# Main.net
KiCad netlist of a schematic drawn in Altium Designer
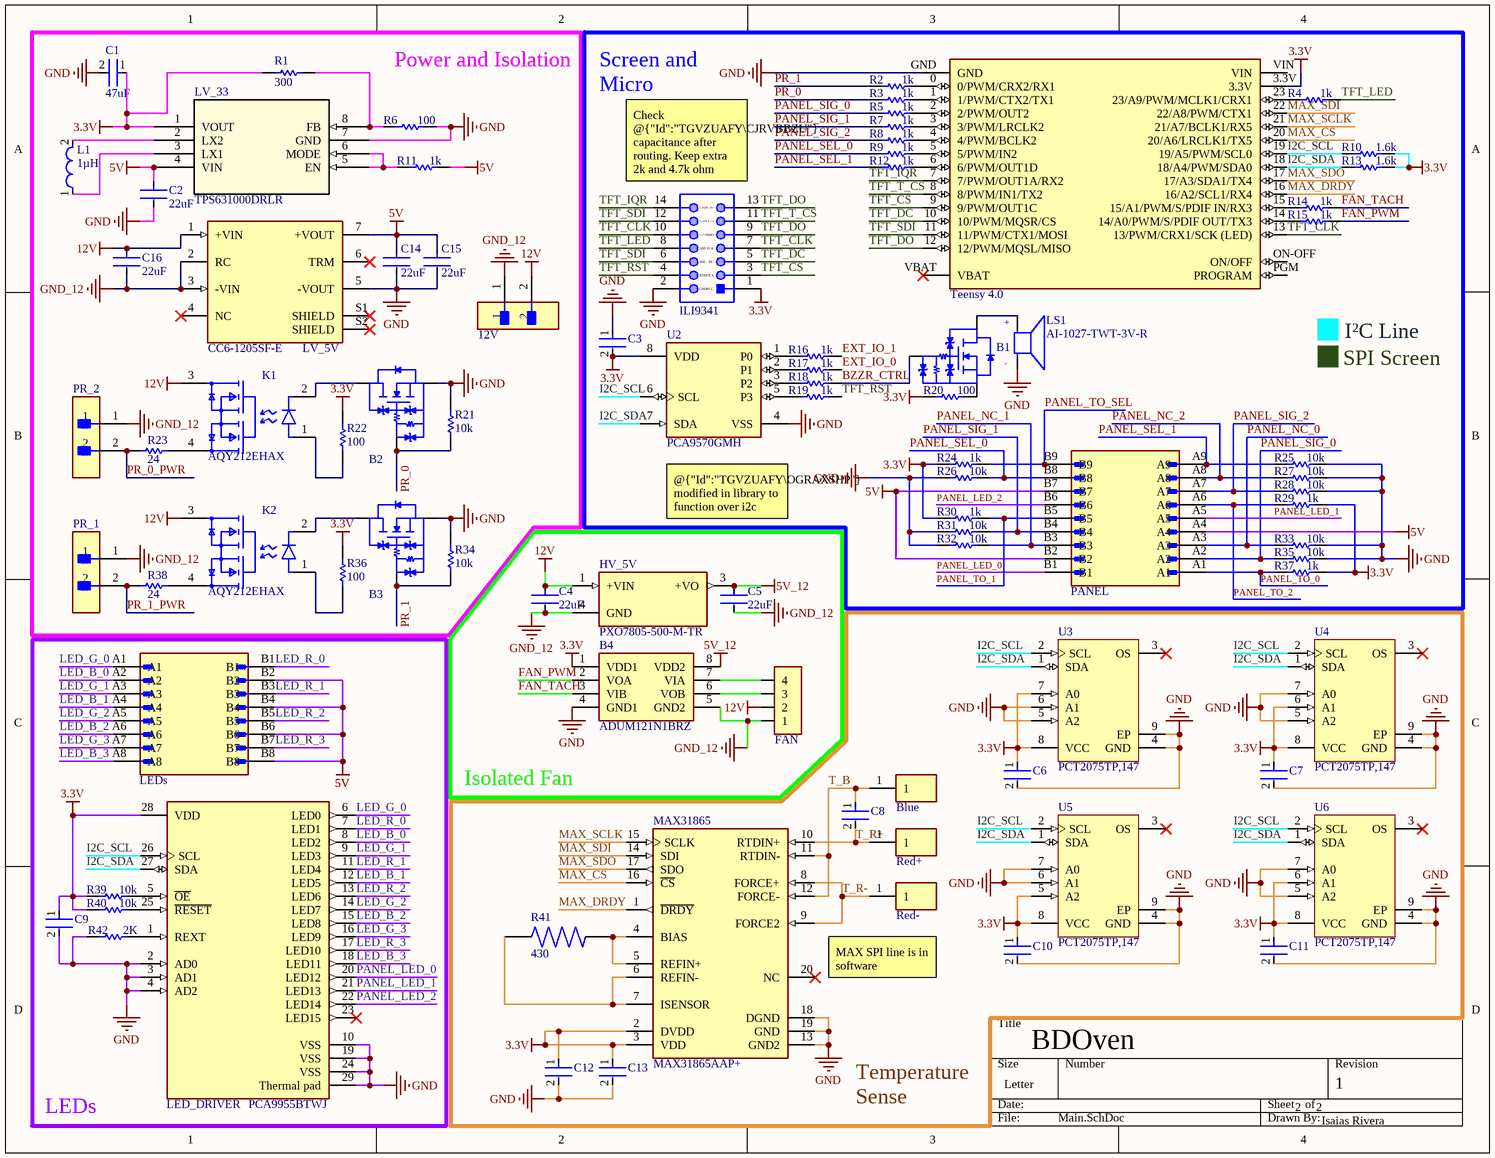
[diagram p0: Main.SchDoc]

(export (version "E")
  (design (tool "Eeschema 10.0.6"))
  (components
    (comp (ref "12V")
      (value "105313-1302")
      (footprint "FP-105313-1102-MFG")
      (description "Nano-Fit Right Angle Header Through Hole 2.50mm Pitch Single Row 2 Circuits 0.76")
      (libsource (lib "") (part "3bc925449376181038e59eaffc5286c_1"))
    )
    (comp (ref "B1")
      (value "SSM3K357R,LF")
      (footprint "SOTFL95P240X88-3N")
      (description "Trans MOSFET N-CH Si 60V 0.65A Automotive 3-Pin SOT-23F T/R")
      (libsource (lib "IIT Motorsports") (part "SSM3K357R,LF"))
    )
    (comp (ref "B2")
      (value "SSM3K357R,LF")
      (footprint "SOTFL95P240X88-3N")
      (description "Trans MOSFET N-CH Si 60V 0.65A Automotive 3-Pin SOT-23F T/R")
      (libsource (lib "IIT Motorsports") (part "SSM3K357R,LF"))
    )
    (comp (ref "B3")
      (value "SSM3K357R,LF")
      (footprint "SOTFL95P240X88-3N")
      (description "Trans MOSFET N-CH Si 60V 0.65A Automotive 3-Pin SOT-23F T/R")
      (libsource (lib "IIT Motorsports") (part "SSM3K357R,LF"))
    )
    (comp (ref "B4")
      (value "ADUM121N1BRZ")
      (footprint "SOIC127P600X175-8N")
      (description "Digital Isolator CMOS 2-CH 150Mbps 8-Pin SOIC N Tube")
      (fields (field (name "MOUSER PART NUMBER") "584-ADUM121N1BRZ"))
      (libsource (lib "IIT Motorsports") (part "ADUM121N1BRZ"))
    )
    (comp (ref "Blue")
      (value "Blue Connector")
      (footprint "8191")
      (description "TERM SCREW 6-32 4 PIN PCB")
      (fields (field (name "MOUSER PART NUMBER") "534-8191") (field (name "MANUFACTURER_PART_NUMBER") "8191"))
      (libsource (lib "IIT Motorsports") (part "8191"))
    )
    (comp (ref "C1")
      (value "47uF")
      (footprint "FP-CL31-IPC_C")
      (description "Cap Ceramic 47uF 10V X5R 20% SMD 1206 85°C Embossed Plastic T/R")
      (libsource (lib "IIT Motorsports") (part "b4654b650e69147ec39a6b967a45e02"))
    )
    (comp (ref "C2")
      (value "22uF")
      (footprint "FP-CL31H-0_2-IPC_C")
      (description "Ceramic capacitor SMD 1206 - 22uF/25V X5R# K +-10% Samsung, RoHS")
      (libsource (lib "IIT Motorsports") (part "11868f565c42a9108669ba33697ecf6"))
    )
    (comp (ref "C3")
      (value "CL10B104JB8NNNC")
      (footprint "FP-CL10-0_1-MFG")
      (description "CAP CER 0.1UF 50V X7R 0603")
      (fields
        (field (name "MANUFACTURER") "Samsung Electro-Mechanics America, Inc")
        (field (name "OCTOPART") "https://octopart.com/cl10b104jb8nnnc-samsung-9302151")
      )
      (libsource (lib "Altium Content Vault") (part "b4654b650e69147ec39a6b967a45e02"))
    )
    (comp (ref "C4")
      (value "22uF")
      (footprint "FP-CL31H-0_2-IPC_C")
      (description "Ceramic capacitor SMD 1206 - 22uF/25V X5R# K +-10% Samsung, RoHS")
      (libsource (lib "IIT Motorsports") (part "11868f565c42a9108669ba33697ecf6"))
    )
    (comp (ref "C5")
      (value "22uF")
      (footprint "FP-CL31H-0_2-IPC_C")
      (description "Ceramic capacitor SMD 1206 - 22uF/25V X5R# K +-10% Samsung, RoHS")
      (libsource (lib "IIT Motorsports") (part "11868f565c42a9108669ba33697ecf6"))
    )
    (comp (ref "C6")
      (value "CL10B104JB8NNNC")
      (footprint "FP-CL10-0_1-MFG")
      (description "CAP CER 0.1UF 50V X7R 0603")
      (fields
        (field (name "MANUFACTURER") "Samsung Electro-Mechanics America, Inc")
        (field (name "OCTOPART") "https://octopart.com/cl10b104jb8nnnc-samsung-9302151")
      )
      (libsource (lib "Altium Content Vault") (part "b4654b650e69147ec39a6b967a45e02"))
    )
    (comp (ref "C7")
      (value "CL10B104JB8NNNC")
      (footprint "FP-CL10-0_1-MFG")
      (description "CAP CER 0.1UF 50V X7R 0603")
      (fields
        (field (name "MANUFACTURER") "Samsung Electro-Mechanics America, Inc")
        (field (name "OCTOPART") "https://octopart.com/cl10b104jb8nnnc-samsung-9302151")
      )
      (libsource (lib "Altium Content Vault") (part "b4654b650e69147ec39a6b967a45e02"))
    )
    (comp (ref "C8")
      (value "CL10B104JB8NNNC")
      (footprint "FP-CL10-0_1-MFG")
      (description "CAP CER 0.1UF 50V X7R 0603")
      (fields
        (field (name "MANUFACTURER") "Samsung Electro-Mechanics America, Inc")
        (field (name "OCTOPART") "https://octopart.com/cl10b104jb8nnnc-samsung-9302151")
      )
      (libsource (lib "Altium Content Vault") (part "b4654b650e69147ec39a6b967a45e02"))
    )
    (comp (ref "C9")
      (value "CL10B104JB8NNNC")
      (footprint "FP-CL10-0_1-MFG")
      (description "CAP CER 0.1UF 50V X7R 0603")
      (fields
        (field (name "MANUFACTURER") "Samsung Electro-Mechanics America, Inc")
        (field (name "OCTOPART") "https://octopart.com/cl10b104jb8nnnc-samsung-9302151")
      )
      (libsource (lib "Altium Content Vault") (part "b4654b650e69147ec39a6b967a45e02"))
    )
    (comp (ref "C10")
      (value "CL10B104JB8NNNC")
      (footprint "FP-CL10-0_1-MFG")
      (description "CAP CER 0.1UF 50V X7R 0603")
      (fields
        (field (name "MANUFACTURER") "Samsung Electro-Mechanics America, Inc")
        (field (name "OCTOPART") "https://octopart.com/cl10b104jb8nnnc-samsung-9302151")
      )
      (libsource (lib "Altium Content Vault") (part "b4654b650e69147ec39a6b967a45e02"))
    )
    (comp (ref "C11")
      (value "CL10B104JB8NNNC")
      (footprint "FP-CL10-0_1-MFG")
      (description "CAP CER 0.1UF 50V X7R 0603")
      (fields
        (field (name "MANUFACTURER") "Samsung Electro-Mechanics America, Inc")
        (field (name "OCTOPART") "https://octopart.com/cl10b104jb8nnnc-samsung-9302151")
      )
      (libsource (lib "Altium Content Vault") (part "b4654b650e69147ec39a6b967a45e02"))
    )
    (comp (ref "C12")
      (value "CL10B104JB8NNNC")
      (footprint "FP-CL10-0_1-MFG")
      (description "CAP CER 0.1UF 50V X7R 0603")
      (fields
        (field (name "MANUFACTURER") "Samsung Electro-Mechanics America, Inc")
        (field (name "OCTOPART") "https://octopart.com/cl10b104jb8nnnc-samsung-9302151")
      )
      (libsource (lib "Altium Content Vault") (part "b4654b650e69147ec39a6b967a45e02"))
    )
    (comp (ref "C13")
      (value "CL10B104JB8NNNC")
      (footprint "FP-CL10-0_1-MFG")
      (description "CAP CER 0.1UF 50V X7R 0603")
      (fields
        (field (name "MANUFACTURER") "Samsung Electro-Mechanics America, Inc")
        (field (name "OCTOPART") "https://octopart.com/cl10b104jb8nnnc-samsung-9302151")
      )
      (libsource (lib "Altium Content Vault") (part "b4654b650e69147ec39a6b967a45e02"))
    )
    (comp (ref "C14")
      (value "22uF")
      (footprint "FP-CL31H-0_2-IPC_C")
      (description "Ceramic capacitor SMD 1206 - 22uF/25V X5R# K +-10% Samsung, RoHS")
      (libsource (lib "IIT Motorsports") (part "11868f565c42a9108669ba33697ecf6"))
    )
    (comp (ref "C15")
      (value "22uF")
      (footprint "FP-CL31H-0_2-IPC_C")
      (description "Ceramic capacitor SMD 1206 - 22uF/25V X5R# K +-10% Samsung, RoHS")
      (libsource (lib "IIT Motorsports") (part "11868f565c42a9108669ba33697ecf6"))
    )
    (comp (ref "C16")
      (value "22uF")
      (footprint "FP-CL31H-0_2-IPC_C")
      (description "Ceramic capacitor SMD 1206 - 22uF/25V X5R# K +-10% Samsung, RoHS")
      (libsource (lib "IIT Motorsports") (part "11868f565c42a9108669ba33697ecf6"))
    )
    (comp (ref "FAN")
      (value "47053-1000")
      (footprint "FP-47053-1000-MFG")
      (description "CONN HEADER VERT 4POS 2.54MM")
      (libsource (lib "IIT Motorsports") (part "299a8cea1bdcbc3624fe62c390fa72c"))
    )
    (comp (ref "HV_5V")
      (value "PXO7805-500-M-TR")
      (footprint "CONV_PXO7805-500-M-TR")
      (description "5 Vdc, 0.5 A, 2.5 W, 6.5~36 Vdc Input Range")
      (fields (field (name "MF") "{'manufacturer': u'CUI'}"))
      (libsource (lib "IIT Motorsports") (part "PXO7805-500-M-TR"))
    )
    (comp (ref "ILI9341")
      (value "61201421721")
      (footprint "61201421721")
      (description "Male Box Header WR-BHD, THT, Angled, pitch 2.54 mm, 14 pins")
      (libsource (lib "IIT Motorsports") (part "WE-CN-2P-M-R14"))
    )
    (comp (ref "K1")
      (value "AQY212EHAX")
      (footprint "FP-AQY212EHAX-MFG")
      (description "Relay Ssr 50MA 1.5V Dc-in 550MA 60V Ac/dc-out 4-PIN DIP SMD T/r")
      (libsource (lib "IIT Motorsports") (part "39108d2c2fe9c6c4263f1aa8ae40286"))
    )
    (comp (ref "K2")
      (value "AQY212EHAX")
      (footprint "FP-AQY212EHAX-MFG")
      (description "Relay Ssr 50MA 1.5V Dc-in 550MA 60V Ac/dc-out 4-PIN DIP SMD T/r")
      (libsource (lib "IIT Motorsports") (part "39108d2c2fe9c6c4263f1aa8ae40286"))
    )
    (comp (ref "L1")
      (value "1µH")
      (footprint "FP-DFE252012C-IPC_C")
      (description "Inductor Power Shielded Wirewound 1uH 20% 1MHz Metal 3.2A 0.042Ohm DCR 1008 T/R")
      (fields (field (name "TOLERANCE") "20%") (field (name "Comment") "DFE252012P-1R0M=P2"))
      (libsource (lib "IIT Motorsports") (part "725321dda6339637d4d059423bc1c3c"))
    )
    (comp (ref "LEDs")
      (value "76383-308LF")
      (footprint "AMPHENOL_91687-306LF")
      (description "Dubox®2.54mm, Board to Board Connector, Shrouded Header, Double Row, Right Angle.")
      (fields (field (name "MF") "{'manufacturer': u'Amphenol ICC (FCI)'}") (field (name "MP") "91687-306LF"))
      (libsource (lib "IIT Motorsports") (part "91687-306LF"))
    )
    (comp (ref "LED_DRIVER")
      (value "PCA9955BTWJ")
      (footprint "FP-SOT1172-3-IPC_A")
      (description "LED DRVR Boost 16-CH Individual RGB PWM 20V 0.03A 28-Pin HTSSOP T/R")
      (libsource (lib "IIT Motorsports") (part "4c3f84e579f246bc22335397bd4750c"))
    )
    (comp (ref "LS1")
      (value "AI-1027-TWT-3V-R")
      (footprint "XDCR_AI-1027-TWT-3V-R")
      (description "Audio Indicator Indicator Electromagnetic 3Vdc 30mA Pin 2Vdc 2500Hz to 2900Hz Through Hole")
      (fields (field (name "MF") "{'manufacturer': u'PUI Audio, Inc.'}"))
      (libsource (lib "IIT Motorsports") (part "AI-1027-TWT-3V-R"))
    )
    (comp (ref "LV_5V")
      (value "CC6-1205SF-E")
      (footprint "CONV_CC6-1205SF-E")
      (description "Module DC-DC 12VIN 1-OUT 5V 1.2A 6W 7-Pin DIP Module")
      (fields (field (name "MF") "{'manufacturer': u'TDK-Lambda'}"))
      (libsource (lib "IIT Motorsports") (part "CC6-1205SF-E"))
    )
    (comp (ref "LV_33")
      (value "TPS631000DRLR")
      (footprint "TPS631000DRLR_TEX")
      (description "1.5-A output current, high power density buck-boost converter 8-SOT-5X3 -40 to 125")
      (fields (field (name "COPYRIGHT") "Copyright (C) 2023 Ultra Librarian. All rights reserved."))
      (libsource (lib "IIT Motorsports") (part "TPS631000DRLR"))
    )
    (comp (ref "MAX31865")
      (value "MAX31865AAP+")
      (footprint "FP-A20-1-IPC_B")
      (description "MAX31865 Series 3.3 V RTD-to-Digital Converter - SSOP-20")
      (libsource (lib "IIT Motorsports") (part "b961fa79eb232f7139144c393e76dba"))
    )
    (comp (ref "PANEL")
      (value "76383-309LF")
      (footprint "AMPHENOL_91687-306LF")
      (description "Dubox®2.54mm, Board to Board Connector, Shrouded Header, Double Row, Right Angle.")
      (fields (field (name "MF") "{'manufacturer': u'Amphenol ICC (FCI)'}") (field (name "MP") "91687-306LF"))
      (libsource (lib "") (part "91687-306LF_1"))
    )
    (comp (ref "PR_1")
      (value "105313-2302")
      (footprint "FP-105313-1102-MFG")
      (description "Nano-Fit Right Angle Header Through Hole 2.50mm Pitch Single Row 2 Circuits 0.76")
      (libsource (lib "IIT Motorsports") (part "3bc925449376181038e59eaffc5286c"))
    )
    (comp (ref "PR_2")
      (value "105313-2302")
      (footprint "FP-105313-1102-MFG")
      (description "Nano-Fit Right Angle Header Through Hole 2.50mm Pitch Single Row 2 Circuits 0.76")
      (libsource (lib "IIT Motorsports") (part "3bc925449376181038e59eaffc5286c"))
    )
    (comp (ref "R1")
      (value "300")
      (footprint "RESC1608X55X30LL15T15")
      (description "RES SMD 300 OHM 1% 1/10W 0603")
      (fields (field (name "TOLERANCE") "1%") (field (name "Comment") "ERJ-3EKF3000V"))
      (libsource (lib "IIT Motorsports") (part "RES"))
    )
    (comp (ref "R2")
      (value "1k")
      (footprint "RESC1608X55X30LL15T15")
      (description "Chip Resistor, 1 KOhm, +/-1%, 0.1 W, -55 to 155 degC, 0603 (1608 Metric)")
      (fields (field (name "TOLERANCE") "1%") (field (name "POWER") "100mW"))
      (libsource (lib "IIT Motorsports") (part "RES"))
    )
    (comp (ref "R3")
      (value "1k")
      (footprint "RESC1608X55X30LL15T15")
      (description "Chip Resistor, 1 KOhm, +/-1%, 0.1 W, -55 to 155 degC, 0603 (1608 Metric)")
      (fields (field (name "TOLERANCE") "1%") (field (name "POWER") "100mW"))
      (libsource (lib "IIT Motorsports") (part "RES"))
    )
    (comp (ref "R4")
      (value "1k")
      (footprint "RESC1608X55X30LL15T15")
      (description "Chip Resistor, 1 KOhm, +/-1%, 0.1 W, -55 to 155 degC, 0603 (1608 Metric)")
      (fields (field (name "TOLERANCE") "1%") (field (name "POWER") "100mW"))
      (libsource (lib "IIT Motorsports") (part "RES"))
    )
    (comp (ref "R5")
      (value "1k")
      (footprint "RESC1608X55X30LL15T15")
      (description "Chip Resistor, 1 KOhm, +/-1%, 0.1 W, -55 to 155 degC, 0603 (1608 Metric)")
      (fields (field (name "TOLERANCE") "1%") (field (name "POWER") "100mW"))
      (libsource (lib "IIT Motorsports") (part "RES"))
    )
    (comp (ref "R6")
      (value "100")
      (footprint "RESC1608X55X30LL15T15")
      (description "Res Thick Film 0603 100 Ohm 1% 1/10W ±100ppm/°C Molded SMD Punched Carrier T/R")
      (fields (field (name "TOLERANCE") "1%") (field (name "Comment") "ERJ-3EKF1000V"))
      (libsource (lib "IIT Motorsports") (part "RES"))
    )
    (comp (ref "R7")
      (value "1k")
      (footprint "RESC1608X55X30LL15T15")
      (description "Chip Resistor, 1 KOhm, +/-1%, 0.1 W, -55 to 155 degC, 0603 (1608 Metric)")
      (fields (field (name "TOLERANCE") "1%") (field (name "POWER") "100mW"))
      (libsource (lib "IIT Motorsports") (part "RES"))
    )
    (comp (ref "R8")
      (value "1k")
      (footprint "RESC1608X55X30LL15T15")
      (description "Chip Resistor, 1 KOhm, +/-1%, 0.1 W, -55 to 155 degC, 0603 (1608 Metric)")
      (fields (field (name "TOLERANCE") "1%") (field (name "POWER") "100mW"))
      (libsource (lib "IIT Motorsports") (part "RES"))
    )
    (comp (ref "R9")
      (value "1k")
      (footprint "RESC1608X55X30LL15T15")
      (description "Chip Resistor, 1 KOhm, +/-1%, 0.1 W, -55 to 155 degC, 0603 (1608 Metric)")
      (fields (field (name "TOLERANCE") "1%") (field (name "POWER") "100mW"))
      (libsource (lib "IIT Motorsports") (part "RES"))
    )
    (comp (ref "R10")
      (value "1.6k")
      (footprint "RESC1608X55X30LL15T15")
      (description "Res Thick Film 0603 1.6K Ohm 1% 1/10W +/-100ppm/ßC Molded SMD Punched Carrier T/R")
      (fields (field (name "TOLERANCE") "1%") (field (name "Comment") "ERJ-3EKF1601V"))
      (libsource (lib "IIT Motorsports") (part "RES"))
    )
    (comp (ref "R11")
      (value "1k")
      (footprint "RESC1608X55X30LL15T15")
      (description "Chip Resistor, 1 KOhm, +/-1%, 0.1 W, -55 to 155 degC, 0603 (1608 Metric)")
      (fields (field (name "TOLERANCE") "1%") (field (name "POWER") "100mW"))
      (libsource (lib "IIT Motorsports") (part "RES"))
    )
    (comp (ref "R12")
      (value "1k")
      (footprint "RESC1608X55X30LL15T15")
      (description "Chip Resistor, 1 KOhm, +/-1%, 0.1 W, -55 to 155 degC, 0603 (1608 Metric)")
      (fields (field (name "TOLERANCE") "1%") (field (name "POWER") "100mW"))
      (libsource (lib "IIT Motorsports") (part "RES"))
    )
    (comp (ref "R13")
      (value "1.6k")
      (footprint "RESC1608X55X30LL15T15")
      (description "Res Thick Film 0603 1.6K Ohm 1% 1/10W +/-100ppm/ßC Molded SMD Punched Carrier T/R")
      (fields (field (name "TOLERANCE") "1%") (field (name "Comment") "ERJ-3EKF1601V"))
      (libsource (lib "IIT Motorsports") (part "RES"))
    )
    (comp (ref "R14")
      (value "1k")
      (footprint "RESC1608X55X30LL15T15")
      (description "Chip Resistor, 1 KOhm, +/-1%, 0.1 W, -55 to 155 degC, 0603 (1608 Metric)")
      (fields (field (name "TOLERANCE") "1%") (field (name "POWER") "100mW"))
      (libsource (lib "IIT Motorsports") (part "RES"))
    )
    (comp (ref "R15")
      (value "1k")
      (footprint "RESC1608X55X30LL15T15")
      (description "Chip Resistor, 1 KOhm, +/-1%, 0.1 W, -55 to 155 degC, 0603 (1608 Metric)")
      (fields (field (name "TOLERANCE") "1%") (field (name "POWER") "100mW"))
      (libsource (lib "IIT Motorsports") (part "RES"))
    )
    (comp (ref "R16")
      (value "1k")
      (footprint "RESC1608X55X30LL15T15")
      (description "Chip Resistor, 1 KOhm, +/-1%, 0.1 W, -55 to 155 degC, 0603 (1608 Metric)")
      (fields (field (name "TOLERANCE") "1%") (field (name "POWER") "100mW"))
      (libsource (lib "IIT Motorsports") (part "RES"))
    )
    (comp (ref "R17")
      (value "1k")
      (footprint "RESC1608X55X30LL15T15")
      (description "Chip Resistor, 1 KOhm, +/-1%, 0.1 W, -55 to 155 degC, 0603 (1608 Metric)")
      (fields (field (name "TOLERANCE") "1%") (field (name "POWER") "100mW"))
      (libsource (lib "IIT Motorsports") (part "RES"))
    )
    (comp (ref "R18")
      (value "1k")
      (footprint "RESC1608X55X30LL15T15")
      (description "Chip Resistor, 1 KOhm, +/-1%, 0.1 W, -55 to 155 degC, 0603 (1608 Metric)")
      (fields (field (name "TOLERANCE") "1%") (field (name "POWER") "100mW"))
      (libsource (lib "IIT Motorsports") (part "RES"))
    )
    (comp (ref "R19")
      (value "1k")
      (footprint "RESC1608X55X30LL15T15")
      (description "Chip Resistor, 1 KOhm, +/-1%, 0.1 W, -55 to 155 degC, 0603 (1608 Metric)")
      (fields (field (name "TOLERANCE") "1%") (field (name "POWER") "100mW"))
      (libsource (lib "IIT Motorsports") (part "RES"))
    )
    (comp (ref "R20")
      (value "100")
      (footprint "RESC1608X55X30LL15T15")
      (description "Res Thick Film 0603 100 Ohm 1% 1/10W ±100ppm/°C Molded SMD Punched Carrier T/R")
      (fields (field (name "TOLERANCE") "1%") (field (name "Comment") "ERJ-3EKF1000V"))
      (libsource (lib "IIT Motorsports") (part "RES"))
    )
    (comp (ref "R21")
      (value "10k")
      (footprint "RESC1609X55X30ML15T15")
      (description "Res Thick Film 0603 10K Ohm 1% 1/10W ±100ppm/°C Molded SMD Punched Carrier T/R")
      (libsource (lib "IIT Motorsports") (part "RES-2"))
    )
    (comp (ref "R22")
      (value "100")
      (footprint "RESC1608X55X30LL15T15")
      (description "Res Thick Film 0603 100 Ohm 1% 1/10W ±100ppm/°C Molded SMD Punched Carrier T/R")
      (fields (field (name "TOLERANCE") "1%") (field (name "Comment") "ERJ-3EKF1000V"))
      (libsource (lib "IIT Motorsports") (part "RES"))
    )
    (comp (ref "R23")
      (value "24")
      (footprint "RES_ERJP08J240V")
      (description "Res Thick Film 1206 24 Ohm 5% 0.33W ±200ppm/°C Molded SMD Punched Carrier T/R")
      (fields (field (name "TOLERANCE") "5%") (field (name "MF") "{'manufacturer': u'Panasonic'}"))
      (libsource (lib "IIT Motorsports") (part "ERJP08J240V"))
    )
    (comp (ref "R24")
      (value "1k")
      (footprint "RESC1608X55X30LL15T15")
      (description "Chip Resistor, 1 KOhm, +/-1%, 0.1 W, -55 to 155 degC, 0603 (1608 Metric)")
      (fields (field (name "TOLERANCE") "1%") (field (name "POWER") "100mW"))
      (libsource (lib "IIT Motorsports") (part "RES"))
    )
    (comp (ref "R25")
      (value "10k")
      (footprint "RESC1609X55X30ML15T15")
      (description "Res Thick Film 0603 10K Ohm 1% 1/10W ±100ppm/°C Molded SMD Punched Carrier T/R")
      (libsource (lib "IIT Motorsports") (part "RES-2"))
    )
    (comp (ref "R26")
      (value "10k")
      (footprint "RESC1609X55X30ML15T15")
      (description "Res Thick Film 0603 10K Ohm 1% 1/10W ±100ppm/°C Molded SMD Punched Carrier T/R")
      (libsource (lib "IIT Motorsports") (part "RES-2"))
    )
    (comp (ref "R27")
      (value "10k")
      (footprint "RESC1609X55X30ML15T15")
      (description "Res Thick Film 0603 10K Ohm 1% 1/10W ±100ppm/°C Molded SMD Punched Carrier T/R")
      (libsource (lib "IIT Motorsports") (part "RES-2"))
    )
    (comp (ref "R28")
      (value "10k")
      (footprint "RESC1609X55X30ML15T15")
      (description "Res Thick Film 0603 10K Ohm 1% 1/10W ±100ppm/°C Molded SMD Punched Carrier T/R")
      (libsource (lib "IIT Motorsports") (part "RES-2"))
    )
    (comp (ref "R29")
      (value "1k")
      (footprint "RESC1608X55X30LL15T15")
      (description "Chip Resistor, 1 KOhm, +/-1%, 0.1 W, -55 to 155 degC, 0603 (1608 Metric)")
      (fields (field (name "TOLERANCE") "1%") (field (name "POWER") "100mW"))
      (libsource (lib "IIT Motorsports") (part "RES"))
    )
    (comp (ref "R30")
      (value "1k")
      (footprint "RESC1608X55X30LL15T15")
      (description "Chip Resistor, 1 KOhm, +/-1%, 0.1 W, -55 to 155 degC, 0603 (1608 Metric)")
      (fields (field (name "TOLERANCE") "1%") (field (name "POWER") "100mW"))
      (libsource (lib "IIT Motorsports") (part "RES"))
    )
    (comp (ref "R31")
      (value "10k")
      (footprint "RESC1609X55X30ML15T15")
      (description "Res Thick Film 0603 10K Ohm 1% 1/10W ±100ppm/°C Molded SMD Punched Carrier T/R")
      (libsource (lib "IIT Motorsports") (part "RES-2"))
    )
    (comp (ref "R32")
      (value "10k")
      (footprint "RESC1609X55X30ML15T15")
      (description "Res Thick Film 0603 10K Ohm 1% 1/10W ±100ppm/°C Molded SMD Punched Carrier T/R")
      (libsource (lib "IIT Motorsports") (part "RES-2"))
    )
    (comp (ref "R33")
      (value "10k")
      (footprint "RESC1609X55X30ML15T15")
      (description "Res Thick Film 0603 10K Ohm 1% 1/10W ±100ppm/°C Molded SMD Punched Carrier T/R")
      (libsource (lib "IIT Motorsports") (part "RES-2"))
    )
    (comp (ref "R34")
      (value "10k")
      (footprint "RESC1609X55X30ML15T15")
      (description "Res Thick Film 0603 10K Ohm 1% 1/10W ±100ppm/°C Molded SMD Punched Carrier T/R")
      (libsource (lib "IIT Motorsports") (part "RES-2"))
    )
    (comp (ref "R35")
      (value "10k")
      (footprint "RESC1609X55X30ML15T15")
      (description "Res Thick Film 0603 10K Ohm 1% 1/10W ±100ppm/°C Molded SMD Punched Carrier T/R")
      (libsource (lib "IIT Motorsports") (part "RES-2"))
    )
    (comp (ref "R36")
      (value "100")
      (footprint "RESC1608X55X30LL15T15")
      (description "Res Thick Film 0603 100 Ohm 1% 1/10W ±100ppm/°C Molded SMD Punched Carrier T/R")
      (fields (field (name "TOLERANCE") "1%") (field (name "Comment") "ERJ-3EKF1000V"))
      (libsource (lib "IIT Motorsports") (part "RES"))
    )
    (comp (ref "R37")
      (value "1k")
      (footprint "RESC1608X55X30LL15T15")
      (description "Chip Resistor, 1 KOhm, +/-1%, 0.1 W, -55 to 155 degC, 0603 (1608 Metric)")
      (fields (field (name "TOLERANCE") "1%") (field (name "POWER") "100mW"))
      (libsource (lib "IIT Motorsports") (part "RES"))
    )
    (comp (ref "R38")
      (value "24")
      (footprint "RES_ERJP08J240V")
      (description "Res Thick Film 1206 24 Ohm 5% 0.33W ±200ppm/°C Molded SMD Punched Carrier T/R")
      (fields (field (name "TOLERANCE") "5%") (field (name "MF") "{'manufacturer': u'Panasonic'}"))
      (libsource (lib "IIT Motorsports") (part "ERJP08J240V"))
    )
    (comp (ref "R39")
      (value "10k")
      (footprint "RESC1609X55X30ML15T15")
      (description "Res Thick Film 0603 10K Ohm 1% 1/10W ±100ppm/°C Molded SMD Punched Carrier T/R")
      (libsource (lib "IIT Motorsports") (part "RES-2"))
    )
    (comp (ref "R40")
      (value "10k")
      (footprint "RESC1609X55X30ML15T15")
      (description "Res Thick Film 0603 10K Ohm 1% 1/10W ±100ppm/°C Molded SMD Punched Carrier T/R")
      (libsource (lib "IIT Motorsports") (part "RES-2"))
    )
    (comp (ref "R41")
      (value "430")
      (footprint "RES_ERJ-PB3B4300V")
      (description "Res SMD 430 Ohm 0.1% 1/5W 0603")
      (fields (field (name "MP") "ERJ-PB3B4300V") (field (name "MF") "{'manufacturer': u'Panasonic'}"))
      (libsource (lib "IIT Motorsports") (part "ERJ-PB3B4300V"))
    )
    (comp (ref "R42")
      (value "2K")
      (footprint "RESC2013X70X40ML20T20")
      (description "RES SMD 2K OHM 1% 1/8W 0805")
      (libsource (lib "IIT Motorsports") (part "RES-2"))
    )
    (comp (ref "Red+")
      (value "Red Connector")
      (footprint "8191")
      (description "TERM SCREW 6-32 4 PIN PCB")
      (fields (field (name "MOUSER PART NUMBER") "534-8191") (field (name "MANUFACTURER_PART_NUMBER") "8191"))
      (libsource (lib "IIT Motorsports") (part "8191"))
    )
    (comp (ref "Red-")
      (value "Red Connector")
      (footprint "8191")
      (description "TERM SCREW 6-32 4 PIN PCB")
      (fields (field (name "MOUSER PART NUMBER") "534-8191") (field (name "MANUFACTURER_PART_NUMBER") "8191"))
      (libsource (lib "IIT Motorsports") (part "8191"))
    )
    (comp (ref "U1")
      (value "Teensy 4.0")
      (footprint "MODULE_DEV-15583")
      (description "RT1062 Teensy 4.0 i.MX ARMÂ® CortexÂ®-M7 MPU Embedded Evaluation Board")
      (fields (field (name "MP") "DEV-15583") (field (name "MF") "{'manufacturer': u'SparkFun Electronics'}"))
      (libsource (lib "IIT Motorsports") (part "DEV-15583"))
    )
    (comp (ref "U2")
      (value "PCA9570GMH")
      (footprint "FP-SOT902-2-MFG")
      (description "I2C/SMBus Interface 100kHz/400kHz 3.6V 8-Pin XQFN T/R")
      (libsource (lib "IIT Motorsports") (part "75db29aab74590c7d6eb7a6560e17c1"))
    )
    (comp (ref "U3")
      (value "PCT2075TP,147")
      (footprint "NXP-SOT1069-2_M")
      (description "Temp Sensor Digital Serial (2-Wire, I2C, SMBus) Automotive 8-Pin HWSON EP T/R")
      (libsource (lib "IIT Motorsports") (part "NXP-PCT2075TP-SOT1069-2-8"))
    )
    (comp (ref "U4")
      (value "PCT2075TP,147")
      (footprint "NXP-SOT1069-2_M")
      (description "Temp Sensor Digital Serial (2-Wire, I2C, SMBus) Automotive 8-Pin HWSON EP T/R")
      (libsource (lib "IIT Motorsports") (part "NXP-PCT2075TP-SOT1069-2-8"))
    )
    (comp (ref "U5")
      (value "PCT2075TP,147")
      (footprint "NXP-SOT1069-2_M")
      (description "Temp Sensor Digital Serial (2-Wire, I2C, SMBus) Automotive 8-Pin HWSON EP T/R")
      (libsource (lib "IIT Motorsports") (part "NXP-PCT2075TP-SOT1069-2-8"))
    )
    (comp (ref "U6")
      (value "PCT2075TP,147")
      (footprint "NXP-SOT1069-2_M")
      (description "Temp Sensor Digital Serial (2-Wire, I2C, SMBus) Automotive 8-Pin HWSON EP T/R")
      (libsource (lib "IIT Motorsports") (part "NXP-PCT2075TP-SOT1069-2-8"))
    )
  )
  (nets
    (net (code "1") (name "/BZZR_CTRL") (class "Default")
      (node (ref "B1") (pin "1") (pinfunction "G_1") (pintype "passive"))
      (node (ref "R18") (pin "1") (pinfunction "1_1") (pintype "passive"))
    )
    (net (code "2") (name "/EXT_IO_0") (class "Default")
      (node (ref "R17") (pin "1") (pinfunction "1_1") (pintype "passive"))
    )
    (net (code "3") (name "/EXT_IO_1") (class "Default")
      (node (ref "R16") (pin "1") (pinfunction "1_1") (pintype "passive"))
    )
    (net (code "4") (name "/FAN_PWM") (class "Default")
      (node (ref "B4") (pin "2") (pinfunction "VOA_2") (pintype "passive"))
      (node (ref "R15") (pin "1") (pinfunction "1_1") (pintype "passive"))
    )
    (net (code "5") (name "/FAN_TACH") (class "Default")
      (node (ref "B4") (pin "3") (pinfunction "VIB_3") (pintype "passive"))
      (node (ref "R14") (pin "1") (pinfunction "1_1") (pintype "passive"))
    )
    (net (code "6") (name "/I2C_SCL") (class "Default")
      (node (ref "LED_DRIVER") (pin "26") (pinfunction "SCL_26") (pintype "input"))
      (node (ref "R10") (pin "1") (pinfunction "1_1") (pintype "passive"))
      (node (ref "U1") (pin "19") (pinfunction "19/A5/PWM/SCL0_19") (pintype "bidirectional"))
      (node (ref "U2") (pin "6") (pinfunction "SCL_6") (pintype "bidirectional"))
      (node (ref "U3") (pin "2") (pinfunction "SCL_2") (pintype "input"))
      (node (ref "U4") (pin "2") (pinfunction "SCL_2") (pintype "input"))
      (node (ref "U5") (pin "2") (pinfunction "SCL_2") (pintype "input"))
      (node (ref "U6") (pin "2") (pinfunction "SCL_2") (pintype "input"))
    )
    (net (code "7") (name "/I2C_SDA") (class "Default")
      (node (ref "LED_DRIVER") (pin "27") (pinfunction "SDA_27") (pintype "bidirectional"))
      (node (ref "R13") (pin "1") (pinfunction "1_1") (pintype "passive"))
      (node (ref "U1") (pin "18") (pinfunction "18/A4/PWM/SDA0_18") (pintype "bidirectional"))
      (node (ref "U2") (pin "7") (pinfunction "SDA_7") (pintype "input"))
      (node (ref "U3") (pin "1") (pinfunction "SDA_1") (pintype "bidirectional"))
      (node (ref "U4") (pin "1") (pinfunction "SDA_1") (pintype "bidirectional"))
      (node (ref "U5") (pin "1") (pinfunction "SDA_1") (pintype "bidirectional"))
      (node (ref "U6") (pin "1") (pinfunction "SDA_1") (pintype "bidirectional"))
    )
    (net (code "8") (name "/LED_B_0") (class "Default")
      (node (ref "LED_DRIVER") (pin "8") (pinfunction "LED2_8") (pintype "output"))
      (node (ref "LEDs") (pin "A2") (pinfunction "A2_A2") (pintype "passive"))
    )
    (net (code "9") (name "/LED_B_1") (class "Default")
      (node (ref "LED_DRIVER") (pin "12") (pinfunction "LED5_12") (pintype "output"))
      (node (ref "LEDs") (pin "A4") (pinfunction "A4_A4") (pintype "passive"))
    )
    (net (code "10") (name "/LED_B_2") (class "Default")
      (node (ref "LED_DRIVER") (pin "15") (pinfunction "LED8_15") (pintype "output"))
      (node (ref "LEDs") (pin "A6") (pinfunction "A6_A6") (pintype "passive"))
    )
    (net (code "11") (name "/LED_B_3") (class "Default")
      (node (ref "LED_DRIVER") (pin "18") (pinfunction "LED11_18") (pintype "output"))
      (node (ref "LEDs") (pin "A8") (pinfunction "A8_A8") (pintype "passive"))
    )
    (net (code "12") (name "/LED_G_0") (class "Default")
      (node (ref "LED_DRIVER") (pin "6") (pinfunction "LED0_6") (pintype "output"))
      (node (ref "LEDs") (pin "A1") (pinfunction "A1_A1") (pintype "passive"))
    )
    (net (code "13") (name "/LED_G_1") (class "Default")
      (node (ref "LED_DRIVER") (pin "9") (pinfunction "LED3_9") (pintype "output"))
      (node (ref "LEDs") (pin "A3") (pinfunction "A3_A3") (pintype "passive"))
    )
    (net (code "14") (name "/LED_G_2") (class "Default")
      (node (ref "LED_DRIVER") (pin "14") (pinfunction "LED7_14") (pintype "output"))
      (node (ref "LEDs") (pin "A5") (pinfunction "A5_A5") (pintype "passive"))
    )
    (net (code "15") (name "/LED_G_3") (class "Default")
      (node (ref "LED_DRIVER") (pin "16") (pinfunction "LED9_16") (pintype "output"))
      (node (ref "LEDs") (pin "A7") (pinfunction "A7_A7") (pintype "passive"))
    )
    (net (code "16") (name "/LED_R_0") (class "Default")
      (node (ref "LED_DRIVER") (pin "7") (pinfunction "LED1_7") (pintype "output"))
      (node (ref "LEDs") (pin "B1") (pinfunction "B1_B1") (pintype "passive"))
    )
    (net (code "17") (name "/LED_R_1") (class "Default")
      (node (ref "LED_DRIVER") (pin "11") (pinfunction "LED4_11") (pintype "output"))
      (node (ref "LEDs") (pin "B3") (pinfunction "B3_B3") (pintype "passive"))
    )
    (net (code "18") (name "/LED_R_2") (class "Default")
      (node (ref "LED_DRIVER") (pin "13") (pinfunction "LED6_13") (pintype "output"))
      (node (ref "LEDs") (pin "B5") (pinfunction "B5_B5") (pintype "passive"))
    )
    (net (code "19") (name "/LED_R_3") (class "Default")
      (node (ref "LED_DRIVER") (pin "17") (pinfunction "LED10_17") (pintype "output"))
      (node (ref "LEDs") (pin "B7") (pinfunction "B7_B7") (pintype "passive"))
    )
    (net (code "20") (name "/MAX_CS") (class "Default")
      (node (ref "MAX31865") (pin "16") (pinfunction "~{CS}_16") (pintype "input"))
      (node (ref "U1") (pin "20") (pinfunction "20/A6/LRCLK1/TX5_20") (pintype "bidirectional"))
    )
    (net (code "21") (name "/MAX_DRDY") (class "Default")
      (node (ref "MAX31865") (pin "1") (pinfunction "~{DRDY}_1") (pintype "output"))
      (node (ref "U1") (pin "16") (pinfunction "16/A2/SCL1/RX4_16") (pintype "bidirectional"))
    )
    (net (code "22") (name "/MAX_SCLK") (class "Default")
      (node (ref "MAX31865") (pin "15") (pinfunction "SCLK_15") (pintype "input"))
      (node (ref "U1") (pin "21") (pinfunction "21/A7/BCLK1/RX5_21") (pintype "bidirectional"))
    )
    (net (code "23") (name "/MAX_SDI") (class "Default")
      (node (ref "MAX31865") (pin "14") (pinfunction "SDI_14") (pintype "input"))
      (node (ref "U1") (pin "22") (pinfunction "22/A8/PWM/CTX1_22") (pintype "bidirectional"))
    )
    (net (code "24") (name "/MAX_SDO") (class "Default")
      (node (ref "MAX31865") (pin "17") (pinfunction "SDO_17") (pintype "output"))
      (node (ref "U1") (pin "17") (pinfunction "17/A3/SDA1/TX4_17") (pintype "bidirectional"))
    )
    (net (code "25") (name "/PANEL_LED_0") (class "Default")
      (node (ref "LED_DRIVER") (pin "20") (pinfunction "LED12_20") (pintype "output"))
      (node (ref "PANEL") (pin "B1") (pinfunction "B1_B1") (pintype "passive"))
    )
    (net (code "26") (name "/PANEL_LED_1") (class "Default")
      (node (ref "LED_DRIVER") (pin "21") (pinfunction "LED13_21") (pintype "output"))
      (node (ref "PANEL") (pin "A5") (pinfunction "A5_A5") (pintype "passive"))
    )
    (net (code "27") (name "/PANEL_LED_2") (class "Default")
      (node (ref "LED_DRIVER") (pin "22") (pinfunction "LED14_22") (pintype "output"))
      (node (ref "PANEL") (pin "B6") (pinfunction "B6_B6") (pintype "passive"))
    )
    (net (code "28") (name "/PANEL_NC_0") (class "Default")
      (node (ref "PANEL") (pin "A3") (pinfunction "A3_A3") (pintype "passive"))
      (node (ref "R33") (pin "2") (pinfunction "2_2") (pintype "passive"))
    )
    (net (code "29") (name "/PANEL_NC_1") (class "Default")
      (node (ref "PANEL") (pin "B3") (pinfunction "B3_B3") (pintype "passive"))
      (node (ref "R32") (pin "1") (pinfunction "1_1") (pintype "passive"))
    )
    (net (code "30") (name "/PANEL_NC_2") (class "Default")
      (node (ref "PANEL") (pin "A8") (pinfunction "A8_A8") (pintype "passive"))
      (node (ref "R27") (pin "2") (pinfunction "2_2") (pintype "passive"))
    )
    (net (code "31") (name "/PANEL_SEL_0") (class "Default")
      (node (ref "PANEL") (pin "B8") (pinfunction "B8_B8") (pintype "passive"))
      (node (ref "R26") (pin "1") (pinfunction "1_1") (pintype "passive"))
      (node (ref "R9") (pin "2") (pinfunction "2_2") (pintype "passive"))
    )
    (net (code "32") (name "/PANEL_SEL_1") (class "Default")
      (node (ref "PANEL") (pin "A9") (pinfunction "A9_A9") (pintype "passive"))
      (node (ref "R12") (pin "2") (pinfunction "2_2") (pintype "passive"))
      (node (ref "R25") (pin "2") (pinfunction "2_2") (pintype "passive"))
    )
    (net (code "33") (name "/PANEL_SIG_0") (class "Default")
      (node (ref "PANEL") (pin "A2") (pinfunction "A2_A2") (pintype "passive"))
      (node (ref "R35") (pin "2") (pinfunction "2_2") (pintype "passive"))
      (node (ref "R5") (pin "2") (pinfunction "2_2") (pintype "passive"))
    )
    (net (code "34") (name "/PANEL_SIG_1") (class "Default")
      (node (ref "PANEL") (pin "B4") (pinfunction "B4_B4") (pintype "passive"))
      (node (ref "R31") (pin "1") (pinfunction "1_1") (pintype "passive"))
      (node (ref "R7") (pin "2") (pinfunction "2_2") (pintype "passive"))
    )
    (net (code "35") (name "/PANEL_SIG_2") (class "Default")
      (node (ref "PANEL") (pin "A7") (pinfunction "A7_A7") (pintype "passive"))
      (node (ref "R28") (pin "2") (pinfunction "2_2") (pintype "passive"))
      (node (ref "R8") (pin "2") (pinfunction "2_2") (pintype "passive"))
    )
    (net (code "36") (name "/PANEL_TO_0") (class "Default")
      (node (ref "PANEL") (pin "A1") (pinfunction "A1_A1") (pintype "passive"))
      (node (ref "R37") (pin "2") (pinfunction "2_2") (pintype "passive"))
    )
    (net (code "37") (name "/PANEL_TO_1") (class "Default")
      (node (ref "PANEL") (pin "B5") (pinfunction "B5_B5") (pintype "passive"))
      (node (ref "R30") (pin "1") (pinfunction "1_1") (pintype "passive"))
    )
    (net (code "38") (name "/PANEL_TO_2") (class "Default")
      (node (ref "PANEL") (pin "A6") (pinfunction "A6_A6") (pintype "passive"))
      (node (ref "R29") (pin "2") (pinfunction "2_2") (pintype "passive"))
    )
    (net (code "39") (name "/PANEL_TO_SEL") (class "Default")
      (node (ref "PANEL") (pin "B9") (pinfunction "B9_B9") (pintype "passive"))
      (node (ref "R24") (pin "1") (pinfunction "1_1") (pintype "passive"))
    )
    (net (code "40") (name "/PR_0") (class "Default")
      (node (ref "B2") (pin "1") (pinfunction "G_1") (pintype "passive"))
      (node (ref "R21") (pin "2") (pinfunction "2_2") (pintype "passive"))
      (node (ref "R3") (pin "2") (pinfunction "2_2") (pintype "passive"))
    )
    (net (code "41") (name "/PR_0_PWR") (class "Default")
      (node (ref "PR_2") (pin "2") (pinfunction "2_2") (pintype "passive"))
      (node (ref "R23") (pin "1") (pinfunction "1_1") (pintype "passive"))
    )
    (net (code "42") (name "/PR_1") (class "Default")
      (node (ref "B3") (pin "1") (pinfunction "G_1") (pintype "passive"))
      (node (ref "R2") (pin "2") (pinfunction "2_2") (pintype "passive"))
      (node (ref "R34") (pin "2") (pinfunction "2_2") (pintype "passive"))
    )
    (net (code "43") (name "/PR_1_PWR") (class "Default")
      (node (ref "PR_1") (pin "2") (pinfunction "2_2") (pintype "passive"))
      (node (ref "R38") (pin "1") (pinfunction "1_1") (pintype "passive"))
    )
    (net (code "44") (name "/TFT_CLK") (class "Default")
      (node (ref "ILI9341") (pin "10") (pinfunction "T_CLK_10") (pintype "passive"))
      (node (ref "ILI9341") (pin "7") (pinfunction "SCK_7") (pintype "passive"))
      (node (ref "U1") (pin "13") (pinfunction "13/PWM/CRX1/SCK_(LED)_13") (pintype "bidirectional"))
    )
    (net (code "45") (name "/TFT_CS") (class "Default")
      (node (ref "ILI9341") (pin "3") (pinfunction "CS_3") (pintype "passive"))
      (node (ref "U1") (pin "9") (pinfunction "9/PWM/OUT1C_9") (pintype "bidirectional"))
    )
    (net (code "46") (name "/TFT_DC") (class "Default")
      (node (ref "ILI9341") (pin "5") (pinfunction "DC_5") (pintype "passive"))
      (node (ref "U1") (pin "10") (pinfunction "10/PWM/MQSR/CS_10") (pintype "bidirectional"))
    )
    (net (code "47") (name "/TFT_DO") (class "Default")
      (node (ref "ILI9341") (pin "13") (pinfunction "T_DO_13") (pintype "passive"))
      (node (ref "ILI9341") (pin "9") (pinfunction "SDO_9") (pintype "passive"))
      (node (ref "U1") (pin "12") (pinfunction "12/PWM/MQSL/MISO_12") (pintype "bidirectional"))
    )
    (net (code "48") (name "/TFT_IQR") (class "Default")
      (node (ref "ILI9341") (pin "14") (pinfunction "T_IQR_14") (pintype "passive"))
      (node (ref "U1") (pin "7") (pinfunction "7/PWM/OUT1A/RX2_7") (pintype "bidirectional"))
    )
    (net (code "49") (name "/TFT_LED") (class "Default")
      (node (ref "ILI9341") (pin "8") (pinfunction "LED_8") (pintype "passive"))
      (node (ref "R4") (pin "1") (pinfunction "1_1") (pintype "passive"))
    )
    (net (code "50") (name "/TFT_RST") (class "Default")
      (node (ref "ILI9341") (pin "4") (pinfunction "RESET_4") (pintype "passive"))
      (node (ref "R19") (pin "1") (pinfunction "1_1") (pintype "passive"))
    )
    (net (code "51") (name "/TFT_SDI") (class "Default")
      (node (ref "ILI9341") (pin "12") (pinfunction "T_DIN_12") (pintype "passive"))
      (node (ref "ILI9341") (pin "6") (pinfunction "SDI_6") (pintype "passive"))
      (node (ref "U1") (pin "11") (pinfunction "11/PWM/CTX1/MOSI_11") (pintype "bidirectional"))
    )
    (net (code "52") (name "/TFT_T_CS") (class "Default")
      (node (ref "ILI9341") (pin "11") (pinfunction "T_CS_11") (pintype "passive"))
      (node (ref "U1") (pin "8") (pinfunction "8/PWM/IN1/TX2_8") (pintype "bidirectional"))
    )
    (net (code "53") (name "/T_B") (class "Default")
      (node (ref "Blue") (pin "1") (pinfunction "1_1") (pintype "passive"))
      (node (ref "C8") (pin "1") (pinfunction "1_1") (pintype "passive"))
      (node (ref "MAX31865") (pin "11") (pinfunction "RTDIN-_11") (pintype "input"))
      (node (ref "MAX31865") (pin "12") (pinfunction "FORCE-_12") (pintype "input"))
    )
    (net (code "54") (name "/T_R+") (class "Default")
      (node (ref "C8") (pin "2") (pinfunction "2_2") (pintype "passive"))
      (node (ref "MAX31865") (pin "10") (pinfunction "RTDIN+_10") (pintype "input"))
      (node (ref "Red+") (pin "1") (pinfunction "1_1") (pintype "passive"))
    )
    (net (code "55") (name "/T_R-") (class "Default")
      (node (ref "MAX31865") (pin "8") (pinfunction "FORCE+_8") (pintype "input"))
      (node (ref "MAX31865") (pin "9") (pinfunction "FORCE2_9") (pintype "input"))
      (node (ref "Red-") (pin "1") (pinfunction "1_1") (pintype "passive"))
    )
    (net (code "56") (name "3.3V") (class "Default")
      (node (ref "B4") (pin "1") (pinfunction "VDD1_1") (pintype "passive"))
      (node (ref "C1") (pin "1") (pinfunction "1_1") (pintype "passive"))
      (node (ref "C10") (pin "1") (pinfunction "1_1") (pintype "passive"))
      (node (ref "C11") (pin "1") (pinfunction "1_1") (pintype "passive"))
      (node (ref "C12") (pin "1") (pinfunction "1_1") (pintype "passive"))
      (node (ref "C13") (pin "1") (pinfunction "1_1") (pintype "passive"))
      (node (ref "C3") (pin "2") (pinfunction "2_2") (pintype "passive"))
      (node (ref "C6") (pin "1") (pinfunction "1_1") (pintype "passive"))
      (node (ref "C7") (pin "1") (pinfunction "1_1") (pintype "passive"))
      (node (ref "C9") (pin "1") (pinfunction "1_1") (pintype "passive"))
      (node (ref "ILI9341") (pin "1") (pinfunction "VCC_1") (pintype "passive"))
      (node (ref "LED_DRIVER") (pin "28") (pinfunction "VDD_28") (pintype "power_in"))
      (node (ref "LV_33") (pin "1") (pinfunction "VOUT_1") (pintype "power_in"))
      (node (ref "MAX31865") (pin "2") (pinfunction "DVDD_2") (pintype "power_in"))
      (node (ref "MAX31865") (pin "3") (pinfunction "VDD_3") (pintype "power_in"))
      (node (ref "R1") (pin "1") (pinfunction "1_1") (pintype "passive"))
      (node (ref "R10") (pin "2") (pinfunction "2_2") (pintype "passive"))
      (node (ref "R13") (pin "2") (pinfunction "2_2") (pintype "passive"))
      (node (ref "R20") (pin "1") (pinfunction "1_1") (pintype "passive"))
      (node (ref "R22") (pin "2") (pinfunction "2_2") (pintype "passive"))
      (node (ref "R24") (pin "2") (pinfunction "2_2") (pintype "passive"))
      (node (ref "R29") (pin "1") (pinfunction "1_1") (pintype "passive"))
      (node (ref "R30") (pin "2") (pinfunction "2_2") (pintype "passive"))
      (node (ref "R36") (pin "2") (pinfunction "2_2") (pintype "passive"))
      (node (ref "R37") (pin "1") (pinfunction "1_1") (pintype "passive"))
      (node (ref "R39") (pin "2") (pinfunction "2_2") (pintype "passive"))
      (node (ref "R40") (pin "2") (pinfunction "2_2") (pintype "passive"))
      (node (ref "U1") (pin "3.3V") (pinfunction "3.3V_3.3V") (pintype "power_in"))
      (node (ref "U2") (pin "8") (pinfunction "VDD_8") (pintype "power_in"))
      (node (ref "U3") (pin "7") (pinfunction "A0_7") (pintype "input"))
      (node (ref "U3") (pin "8") (pinfunction "VCC_8") (pintype "power_in"))
      (node (ref "U4") (pin "6") (pinfunction "A1_6") (pintype "input"))
      (node (ref "U4") (pin "8") (pinfunction "VCC_8") (pintype "power_in"))
      (node (ref "U5") (pin "5") (pinfunction "A2_5") (pintype "input"))
      (node (ref "U5") (pin "8") (pinfunction "VCC_8") (pintype "power_in"))
      (node (ref "U6") (pin "6") (pinfunction "A1_6") (pintype "input"))
      (node (ref "U6") (pin "8") (pinfunction "VCC_8") (pintype "power_in"))
    )
    (net (code "57") (name "5V") (class "Default")
      (node (ref "C14") (pin "1") (pinfunction "1_1") (pintype "passive"))
      (node (ref "C15") (pin "1") (pinfunction "1_1") (pintype "passive"))
      (node (ref "C2") (pin "1") (pinfunction "1_1") (pintype "passive"))
      (node (ref "LEDs") (pin "B2") (pinfunction "B2_B2") (pintype "passive"))
      (node (ref "LEDs") (pin "B4") (pinfunction "B4_B4") (pintype "passive"))
      (node (ref "LEDs") (pin "B6") (pinfunction "B6_B6") (pintype "passive"))
      (node (ref "LEDs") (pin "B8") (pinfunction "B8_B8") (pintype "passive"))
      (node (ref "LV_33") (pin "4") (pinfunction "VIN_4") (pintype "power_in"))
      (node (ref "LV_5V") (pin "7") (pinfunction "+VOUT_7") (pintype "power_in"))
      (node (ref "PANEL") (pin "A4") (pinfunction "A4_A4") (pintype "passive"))
      (node (ref "PANEL") (pin "B2") (pinfunction "B2_B2") (pintype "passive"))
      (node (ref "PANEL") (pin "B7") (pinfunction "B7_B7") (pintype "passive"))
      (node (ref "R11") (pin "1") (pinfunction "1_1") (pintype "passive"))
    )
    (net (code "58") (name "5V_12") (class "Default")
      (node (ref "B4") (pin "8") (pinfunction "VDD2_8") (pintype "passive"))
      (node (ref "C5") (pin "1") (pinfunction "1_1") (pintype "passive"))
      (node (ref "HV_5V") (pin "3") (pinfunction "+VO_3") (pintype "output"))
    )
    (net (code "59") (name "12V") (class "Default")
      (node (ref "12V") (pin "2") (pinfunction "2_2") (pintype "passive"))
      (node (ref "C16") (pin "1") (pinfunction "1_1") (pintype "passive"))
      (node (ref "C4") (pin "1") (pinfunction "1_1") (pintype "passive"))
      (node (ref "FAN") (pin "2") (pinfunction "2_2") (pintype "passive"))
      (node (ref "HV_5V") (pin "1") (pinfunction "+VIN_1") (pintype "input"))
      (node (ref "K1") (pin "3") (pinfunction "1_DRAIN_3") (pintype "passive"))
      (node (ref "K2") (pin "3") (pinfunction "1_DRAIN_3") (pintype "passive"))
      (node (ref "LV_5V") (pin "1") (pinfunction "+VIN_1") (pintype "input"))
    )
    (net (code "60") (name "GND") (class "Default")
      (node (ref "B2") (pin "2") (pinfunction "S_2") (pintype "passive"))
      (node (ref "B3") (pin "2") (pinfunction "S_2") (pintype "passive"))
      (node (ref "B4") (pin "4") (pinfunction "GND1_4") (pintype "passive"))
      (node (ref "C1") (pin "2") (pinfunction "2_2") (pintype "passive"))
      (node (ref "C10") (pin "2") (pinfunction "2_2") (pintype "passive"))
      (node (ref "C11") (pin "2") (pinfunction "2_2") (pintype "passive"))
      (node (ref "C12") (pin "2") (pinfunction "2_2") (pintype "passive"))
      (node (ref "C13") (pin "2") (pinfunction "2_2") (pintype "passive"))
      (node (ref "C14") (pin "2") (pinfunction "2_2") (pintype "passive"))
      (node (ref "C15") (pin "2") (pinfunction "2_2") (pintype "passive"))
      (node (ref "C2") (pin "2") (pinfunction "2_2") (pintype "passive"))
      (node (ref "C3") (pin "1") (pinfunction "1_1") (pintype "passive"))
      (node (ref "C6") (pin "2") (pinfunction "2_2") (pintype "passive"))
      (node (ref "C7") (pin "2") (pinfunction "2_2") (pintype "passive"))
      (node (ref "C9") (pin "2") (pinfunction "2_2") (pintype "passive"))
      (node (ref "ILI9341") (pin "2") (pinfunction "GND_2") (pintype "passive"))
      (node (ref "LED_DRIVER") (pin "10") (pinfunction "VSS_10") (pintype "passive"))
      (node (ref "LED_DRIVER") (pin "19") (pinfunction "VSS_19") (pintype "passive"))
      (node (ref "LED_DRIVER") (pin "2") (pinfunction "AD0_2") (pintype "input"))
      (node (ref "LED_DRIVER") (pin "24") (pinfunction "VSS_24") (pintype "passive"))
      (node (ref "LED_DRIVER") (pin "29") (pinfunction "Thermal_pad_29") (pintype "passive"))
      (node (ref "LED_DRIVER") (pin "3") (pinfunction "AD1_3") (pintype "input"))
      (node (ref "LED_DRIVER") (pin "4") (pinfunction "AD2_4") (pintype "input"))
      (node (ref "LS1") (pin "N") (pinfunction "N_N") (pintype "passive"))
      (node (ref "LV_33") (pin "7") (pinfunction "GND_7") (pintype "power_in"))
      (node (ref "LV_5V") (pin "5") (pinfunction "-VOUT_5") (pintype "passive"))
      (node (ref "MAX31865") (pin "13") (pinfunction "GND2_13") (pintype "passive"))
      (node (ref "MAX31865") (pin "18") (pinfunction "DGND_18") (pintype "passive"))
      (node (ref "MAX31865") (pin "19") (pinfunction "GND_19") (pintype "passive"))
      (node (ref "R21") (pin "1") (pinfunction "1_1") (pintype "passive"))
      (node (ref "R25") (pin "1") (pinfunction "1_1") (pintype "passive"))
      (node (ref "R26") (pin "2") (pinfunction "2_2") (pintype "passive"))
      (node (ref "R27") (pin "1") (pinfunction "1_1") (pintype "passive"))
      (node (ref "R28") (pin "1") (pinfunction "1_1") (pintype "passive"))
      (node (ref "R31") (pin "2") (pinfunction "2_2") (pintype "passive"))
      (node (ref "R32") (pin "2") (pinfunction "2_2") (pintype "passive"))
      (node (ref "R33") (pin "1") (pinfunction "1_1") (pintype "passive"))
      (node (ref "R34") (pin "1") (pinfunction "1_1") (pintype "passive"))
      (node (ref "R35") (pin "1") (pinfunction "1_1") (pintype "passive"))
      (node (ref "R42") (pin "1") (pinfunction "1_1") (pintype "passive"))
      (node (ref "R6") (pin "2") (pinfunction "2_2") (pintype "passive"))
      (node (ref "U1") (pin "GND") (pinfunction "GND_GND") (pintype "power_in"))
      (node (ref "U2") (pin "4") (pinfunction "VSS_4") (pintype "power_in"))
      (node (ref "U3") (pin "4") (pinfunction "GND_4") (pintype "passive"))
      (node (ref "U3") (pin "5") (pinfunction "A2_5") (pintype "input"))
      (node (ref "U3") (pin "6") (pinfunction "A1_6") (pintype "input"))
      (node (ref "U3") (pin "9") (pinfunction "EP_9") (pintype "passive"))
      (node (ref "U4") (pin "4") (pinfunction "GND_4") (pintype "passive"))
      (node (ref "U4") (pin "5") (pinfunction "A2_5") (pintype "input"))
      (node (ref "U4") (pin "7") (pinfunction "A0_7") (pintype "input"))
      (node (ref "U4") (pin "9") (pinfunction "EP_9") (pintype "passive"))
      (node (ref "U5") (pin "4") (pinfunction "GND_4") (pintype "passive"))
      (node (ref "U5") (pin "6") (pinfunction "A1_6") (pintype "input"))
      (node (ref "U5") (pin "7") (pinfunction "A0_7") (pintype "input"))
      (node (ref "U5") (pin "9") (pinfunction "EP_9") (pintype "passive"))
      (node (ref "U6") (pin "4") (pinfunction "GND_4") (pintype "passive"))
      (node (ref "U6") (pin "5") (pinfunction "A2_5") (pintype "input"))
      (node (ref "U6") (pin "7") (pinfunction "A0_7") (pintype "input"))
      (node (ref "U6") (pin "9") (pinfunction "EP_9") (pintype "passive"))
    )
    (net (code "61") (name "GND_12") (class "Default")
      (node (ref "12V") (pin "1") (pinfunction "1_1") (pintype "passive"))
      (node (ref "B4") (pin "5") (pinfunction "GND2_5") (pintype "passive"))
      (node (ref "C16") (pin "2") (pinfunction "2_2") (pintype "passive"))
      (node (ref "C4") (pin "2") (pinfunction "2_2") (pintype "passive"))
      (node (ref "C5") (pin "2") (pinfunction "2_2") (pintype "passive"))
      (node (ref "FAN") (pin "1") (pinfunction "1_1") (pintype "passive"))
      (node (ref "HV_5V") (pin "4") (pinfunction "GND_4") (pintype "power_in"))
      (node (ref "LV_5V") (pin "2") (pinfunction "RC_2") (pintype "passive"))
      (node (ref "LV_5V") (pin "3") (pinfunction "-VIN_3") (pintype "input"))
      (node (ref "PR_1") (pin "1") (pinfunction "1_1") (pintype "passive"))
      (node (ref "PR_2") (pin "1") (pinfunction "1_1") (pintype "passive"))
    )
    (net (code "62") (name "Net-(B1-D)") (class "Default")
      (node (ref "B1") (pin "3") (pinfunction "D_3") (pintype "passive"))
      (node (ref "LS1") (pin "P") (pinfunction "P_P") (pintype "passive"))
    )
    (net (code "63") (name "Net-(B1-S)") (class "Default")
      (node (ref "B1") (pin "2") (pinfunction "S_2") (pintype "passive"))
      (node (ref "R20") (pin "2") (pinfunction "2_2") (pintype "passive"))
    )
    (net (code "64") (name "Net-(B2-D)") (class "Default")
      (node (ref "B2") (pin "3") (pinfunction "D_3") (pintype "passive"))
      (node (ref "K1") (pin "2") (pinfunction "C_2") (pintype "passive"))
    )
    (net (code "65") (name "Net-(B3-D)") (class "Default")
      (node (ref "B3") (pin "3") (pinfunction "D_3") (pintype "passive"))
      (node (ref "K2") (pin "2") (pinfunction "C_2") (pintype "passive"))
    )
    (net (code "66") (name "Net-(B4-VIA)") (class "Default")
      (node (ref "B4") (pin "7") (pinfunction "VIA_7") (pintype "passive"))
      (node (ref "FAN") (pin "4") (pinfunction "4_4") (pintype "passive"))
    )
    (net (code "67") (name "Net-(B4-VOB)") (class "Default")
      (node (ref "B4") (pin "6") (pinfunction "VOB_6") (pintype "passive"))
      (node (ref "FAN") (pin "3") (pinfunction "3_3") (pintype "passive"))
    )
    (net (code "68") (name "Net-(K1-2_DRAIN)") (class "Default")
      (node (ref "K1") (pin "4") (pinfunction "2_DRAIN_4") (pintype "passive"))
      (node (ref "R23") (pin "2") (pinfunction "2_2") (pintype "passive"))
    )
    (net (code "69") (name "Net-(K1-A)") (class "Default")
      (node (ref "K1") (pin "1") (pinfunction "A_1") (pintype "passive"))
      (node (ref "R22") (pin "1") (pinfunction "1_1") (pintype "passive"))
    )
    (net (code "70") (name "Net-(K2-2_DRAIN)") (class "Default")
      (node (ref "K2") (pin "4") (pinfunction "2_DRAIN_4") (pintype "passive"))
      (node (ref "R38") (pin "2") (pinfunction "2_2") (pintype "passive"))
    )
    (net (code "71") (name "Net-(K2-A)") (class "Default")
      (node (ref "K2") (pin "1") (pinfunction "A_1") (pintype "passive"))
      (node (ref "R36") (pin "1") (pinfunction "1_1") (pintype "passive"))
    )
    (net (code "72") (name "Net-(LED_DRIVER-REXT)") (class "Default")
      (node (ref "LED_DRIVER") (pin "1") (pinfunction "REXT_1") (pintype "input"))
      (node (ref "R42") (pin "2") (pinfunction "2_2") (pintype "passive"))
    )
    (net (code "73") (name "Net-(LED_DRIVER-~{OE})") (class "Default")
      (node (ref "LED_DRIVER") (pin "5") (pinfunction "~{OE}_5") (pintype "input"))
      (node (ref "R39") (pin "1") (pinfunction "1_1") (pintype "passive"))
    )
    (net (code "74") (name "Net-(LED_DRIVER-~{RESET})") (class "Default")
      (node (ref "LED_DRIVER") (pin "25") (pinfunction "~{RESET}_25") (pintype "input"))
      (node (ref "R40") (pin "1") (pinfunction "1_1") (pintype "passive"))
    )
    (net (code "75") (name "Net-(LV_33-EN)") (class "Default")
      (node (ref "LV_33") (pin "5") (pinfunction "EN_5") (pintype "input"))
      (node (ref "LV_33") (pin "6") (pinfunction "MODE_6") (pintype "input"))
      (node (ref "R11") (pin "2") (pinfunction "2_2") (pintype "passive"))
    )
    (net (code "76") (name "Net-(LV_33-FB)") (class "Default")
      (node (ref "LV_33") (pin "8") (pinfunction "FB_8") (pintype "input"))
      (node (ref "R1") (pin "2") (pinfunction "2_2") (pintype "passive"))
      (node (ref "R6") (pin "1") (pinfunction "1_1") (pintype "passive"))
    )
    (net (code "77") (name "Net-(LV_33-LX1)") (class "Default")
      (node (ref "L1") (pin "1") (pinfunction "1_1") (pintype "passive"))
      (node (ref "LV_33") (pin "3") (pinfunction "LX1_3") (pintype "power_in"))
    )
    (net (code "78") (name "Net-(LV_33-LX2)") (class "Default")
      (node (ref "L1") (pin "2") (pinfunction "2_2") (pintype "passive"))
      (node (ref "LV_33") (pin "2") (pinfunction "LX2_2") (pintype "power_in"))
    )
    (net (code "79") (name "Net-(MAX31865-BIAS)") (class "Default")
      (node (ref "MAX31865") (pin "4") (pinfunction "BIAS_4") (pintype "passive"))
      (node (ref "MAX31865") (pin "5") (pinfunction "REFIN+_5") (pintype "passive"))
      (node (ref "R41") (pin "1") (pinfunction "1_1") (pintype "passive"))
    )
    (net (code "80") (name "Net-(MAX31865-ISENSOR)") (class "Default")
      (node (ref "MAX31865") (pin "6") (pinfunction "REFIN-_6") (pintype "passive"))
      (node (ref "MAX31865") (pin "7") (pinfunction "ISENSOR_7") (pintype "passive"))
      (node (ref "R41") (pin "2") (pinfunction "2_2") (pintype "passive"))
    )
    (net (code "81") (name "Net-(U1-0{slash}PWM{slash}CRX2{slash}RX1)") (class "Default")
      (node (ref "R2") (pin "1") (pinfunction "1_1") (pintype "passive"))
      (node (ref "U1") (pin "0") (pinfunction "0/PWM/CRX2/RX1_0") (pintype "bidirectional"))
    )
    (net (code "82") (name "Net-(U1-1{slash}PWM{slash}CTX2{slash}TX1)") (class "Default")
      (node (ref "R3") (pin "1") (pinfunction "1_1") (pintype "passive"))
      (node (ref "U1") (pin "1") (pinfunction "1/PWM/CTX2/TX1_1") (pintype "bidirectional"))
    )
    (net (code "83") (name "Net-(U1-2{slash}PWM{slash}OUT2)") (class "Default")
      (node (ref "R5") (pin "1") (pinfunction "1_1") (pintype "passive"))
      (node (ref "U1") (pin "2") (pinfunction "2/PWM/OUT2_2") (pintype "bidirectional"))
    )
    (net (code "84") (name "Net-(U1-3{slash}PWM{slash}LRCLK2)") (class "Default")
      (node (ref "R7") (pin "1") (pinfunction "1_1") (pintype "passive"))
      (node (ref "U1") (pin "3") (pinfunction "3/PWM/LRCLK2_3") (pintype "bidirectional"))
    )
    (net (code "85") (name "Net-(U1-4{slash}PWM{slash}BCLK2)") (class "Default")
      (node (ref "R8") (pin "1") (pinfunction "1_1") (pintype "passive"))
      (node (ref "U1") (pin "4") (pinfunction "4/PWM/BCLK2_4") (pintype "bidirectional"))
    )
    (net (code "86") (name "Net-(U1-5{slash}PWM{slash}IN2)") (class "Default")
      (node (ref "R9") (pin "1") (pinfunction "1_1") (pintype "passive"))
      (node (ref "U1") (pin "5") (pinfunction "5/PWM/IN2_5") (pintype "bidirectional"))
    )
    (net (code "87") (name "Net-(U1-6{slash}PWM{slash}OUT1D)") (class "Default")
      (node (ref "R12") (pin "1") (pinfunction "1_1") (pintype "passive"))
      (node (ref "U1") (pin "6") (pinfunction "6/PWM/OUT1D_6") (pintype "bidirectional"))
    )
    (net (code "88") (name "Net-(U1-14{slash}A0{slash}PWM{slash}S{slash}PDIF_OUT{slash}TX3)") (class "Default")
      (node (ref "R15") (pin "2") (pinfunction "2_2") (pintype "passive"))
      (node (ref "U1") (pin "14") (pinfunction "14/A0/PWM/S/PDIF_OUT/TX3_14") (pintype "bidirectional"))
    )
    (net (code "89") (name "Net-(U1-15{slash}A1{slash}PWM{slash}S{slash}PDIF_IN{slash}RX3)") (class "Default")
      (node (ref "R14") (pin "2") (pinfunction "2_2") (pintype "passive"))
      (node (ref "U1") (pin "15") (pinfunction "15/A1/PWM/S/PDIF_IN/RX3_15") (pintype "bidirectional"))
    )
    (net (code "90") (name "Net-(U1-23{slash}A9{slash}PWM{slash}MCLK1{slash}CRX1)") (class "Default")
      (node (ref "R4") (pin "2") (pinfunction "2_2") (pintype "passive"))
      (node (ref "U1") (pin "23") (pinfunction "23/A9/PWM/MCLK1/CRX1_23") (pintype "bidirectional"))
    )
    (net (code "91") (name "Net-(U2-P0)") (class "Default")
      (node (ref "R16") (pin "2") (pinfunction "2_2") (pintype "passive"))
      (node (ref "U2") (pin "1") (pinfunction "P0_1") (pintype "bidirectional"))
    )
    (net (code "92") (name "Net-(U2-P1)") (class "Default")
      (node (ref "R17") (pin "2") (pinfunction "2_2") (pintype "passive"))
      (node (ref "U2") (pin "2") (pinfunction "P1_2") (pintype "bidirectional"))
    )
    (net (code "93") (name "Net-(U2-P2)") (class "Default")
      (node (ref "R18") (pin "2") (pinfunction "2_2") (pintype "passive"))
      (node (ref "U2") (pin "3") (pinfunction "P2_3") (pintype "bidirectional"))
    )
    (net (code "94") (name "Net-(U2-P3)") (class "Default")
      (node (ref "R19") (pin "2") (pinfunction "2_2") (pintype "passive"))
      (node (ref "U2") (pin "5") (pinfunction "P3_5") (pintype "bidirectional"))
    )
    (net (code "95") (name "unconnected-(LED_DRIVER-LED15-Pad23)") (class "Default")
      (node (ref "LED_DRIVER") (pin "23") (pinfunction "LED15_23") (pintype "output+no_connect"))
    )
    (net (code "96") (name "unconnected-(LV_5V-NC-Pad4)") (class "Default")
      (node (ref "LV_5V") (pin "4") (pinfunction "NC_4") (pintype "passive+no_connect"))
    )
    (net (code "97") (name "unconnected-(LV_5V-SHIELD-PadS1)") (class "Default")
      (node (ref "LV_5V") (pin "S1") (pinfunction "SHIELD_S1") (pintype "passive+no_connect"))
    )
    (net (code "98") (name "unconnected-(LV_5V-SHIELD-PadS2)") (class "Default")
      (node (ref "LV_5V") (pin "S2") (pinfunction "SHIELD_S2") (pintype "passive+no_connect"))
    )
    (net (code "99") (name "unconnected-(LV_5V-TRM-Pad6)") (class "Default")
      (node (ref "LV_5V") (pin "6") (pinfunction "TRM_6") (pintype "passive+no_connect"))
    )
    (net (code "100") (name "unconnected-(MAX31865-NC-Pad20)") (class "Default")
      (node (ref "MAX31865") (pin "20") (pinfunction "NC_20") (pintype "passive+no_connect"))
    )
    (net (code "101") (name "unconnected-(U1-ON{slash}OFF-PadON-OFF)") (class "Default")
      (node (ref "U1") (pin "ON-OFF") (pinfunction "ON/OFF_ON-OFF") (pintype "bidirectional"))
    )
    (net (code "102") (name "unconnected-(U1-PROGRAM-PadPGM)") (class "Default")
      (node (ref "U1") (pin "PGM") (pinfunction "PROGRAM_PGM") (pintype "bidirectional"))
    )
    (net (code "103") (name "unconnected-(U1-PadVBAT)") (class "Default")
      (node (ref "U1") (pin "VBAT") (pinfunction "VBAT_VBAT") (pintype "power_in+no_connect"))
    )
    (net (code "104") (name "unconnected-(U1-PadVIN)") (class "Default")
      (node (ref "U1") (pin "VIN") (pinfunction "VIN_VIN") (pintype "power_in"))
    )
    (net (code "105") (name "unconnected-(U3-OS-Pad3)") (class "Default")
      (node (ref "U3") (pin "3") (pinfunction "OS_3") (pintype "open_collector+no_connect"))
    )
    (net (code "106") (name "unconnected-(U4-OS-Pad3)") (class "Default")
      (node (ref "U4") (pin "3") (pinfunction "OS_3") (pintype "open_collector+no_connect"))
    )
    (net (code "107") (name "unconnected-(U5-OS-Pad3)") (class "Default")
      (node (ref "U5") (pin "3") (pinfunction "OS_3") (pintype "open_collector+no_connect"))
    )
    (net (code "108") (name "unconnected-(U6-OS-Pad3)") (class "Default")
      (node (ref "U6") (pin "3") (pinfunction "OS_3") (pintype "open_collector+no_connect"))
    )
  )
)
